# Status_Board.net
KiCad netlist of a schematic drawn in EAGLE
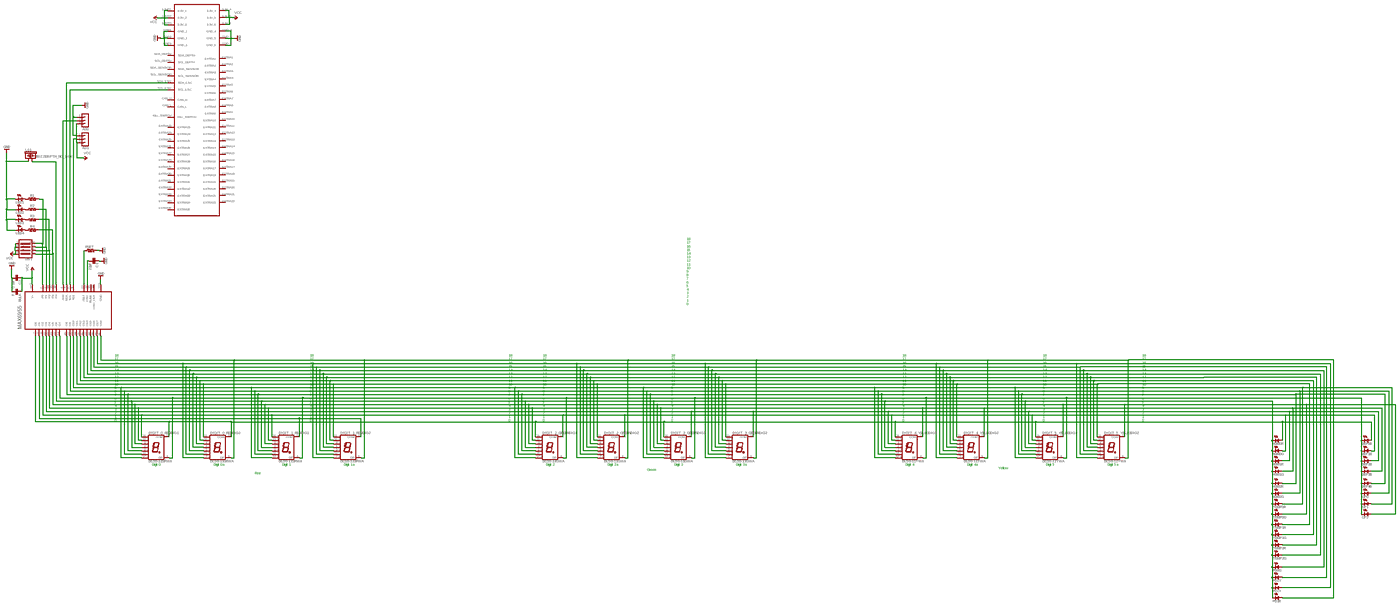
[diagram p0: schematic, sheet 1, overview]
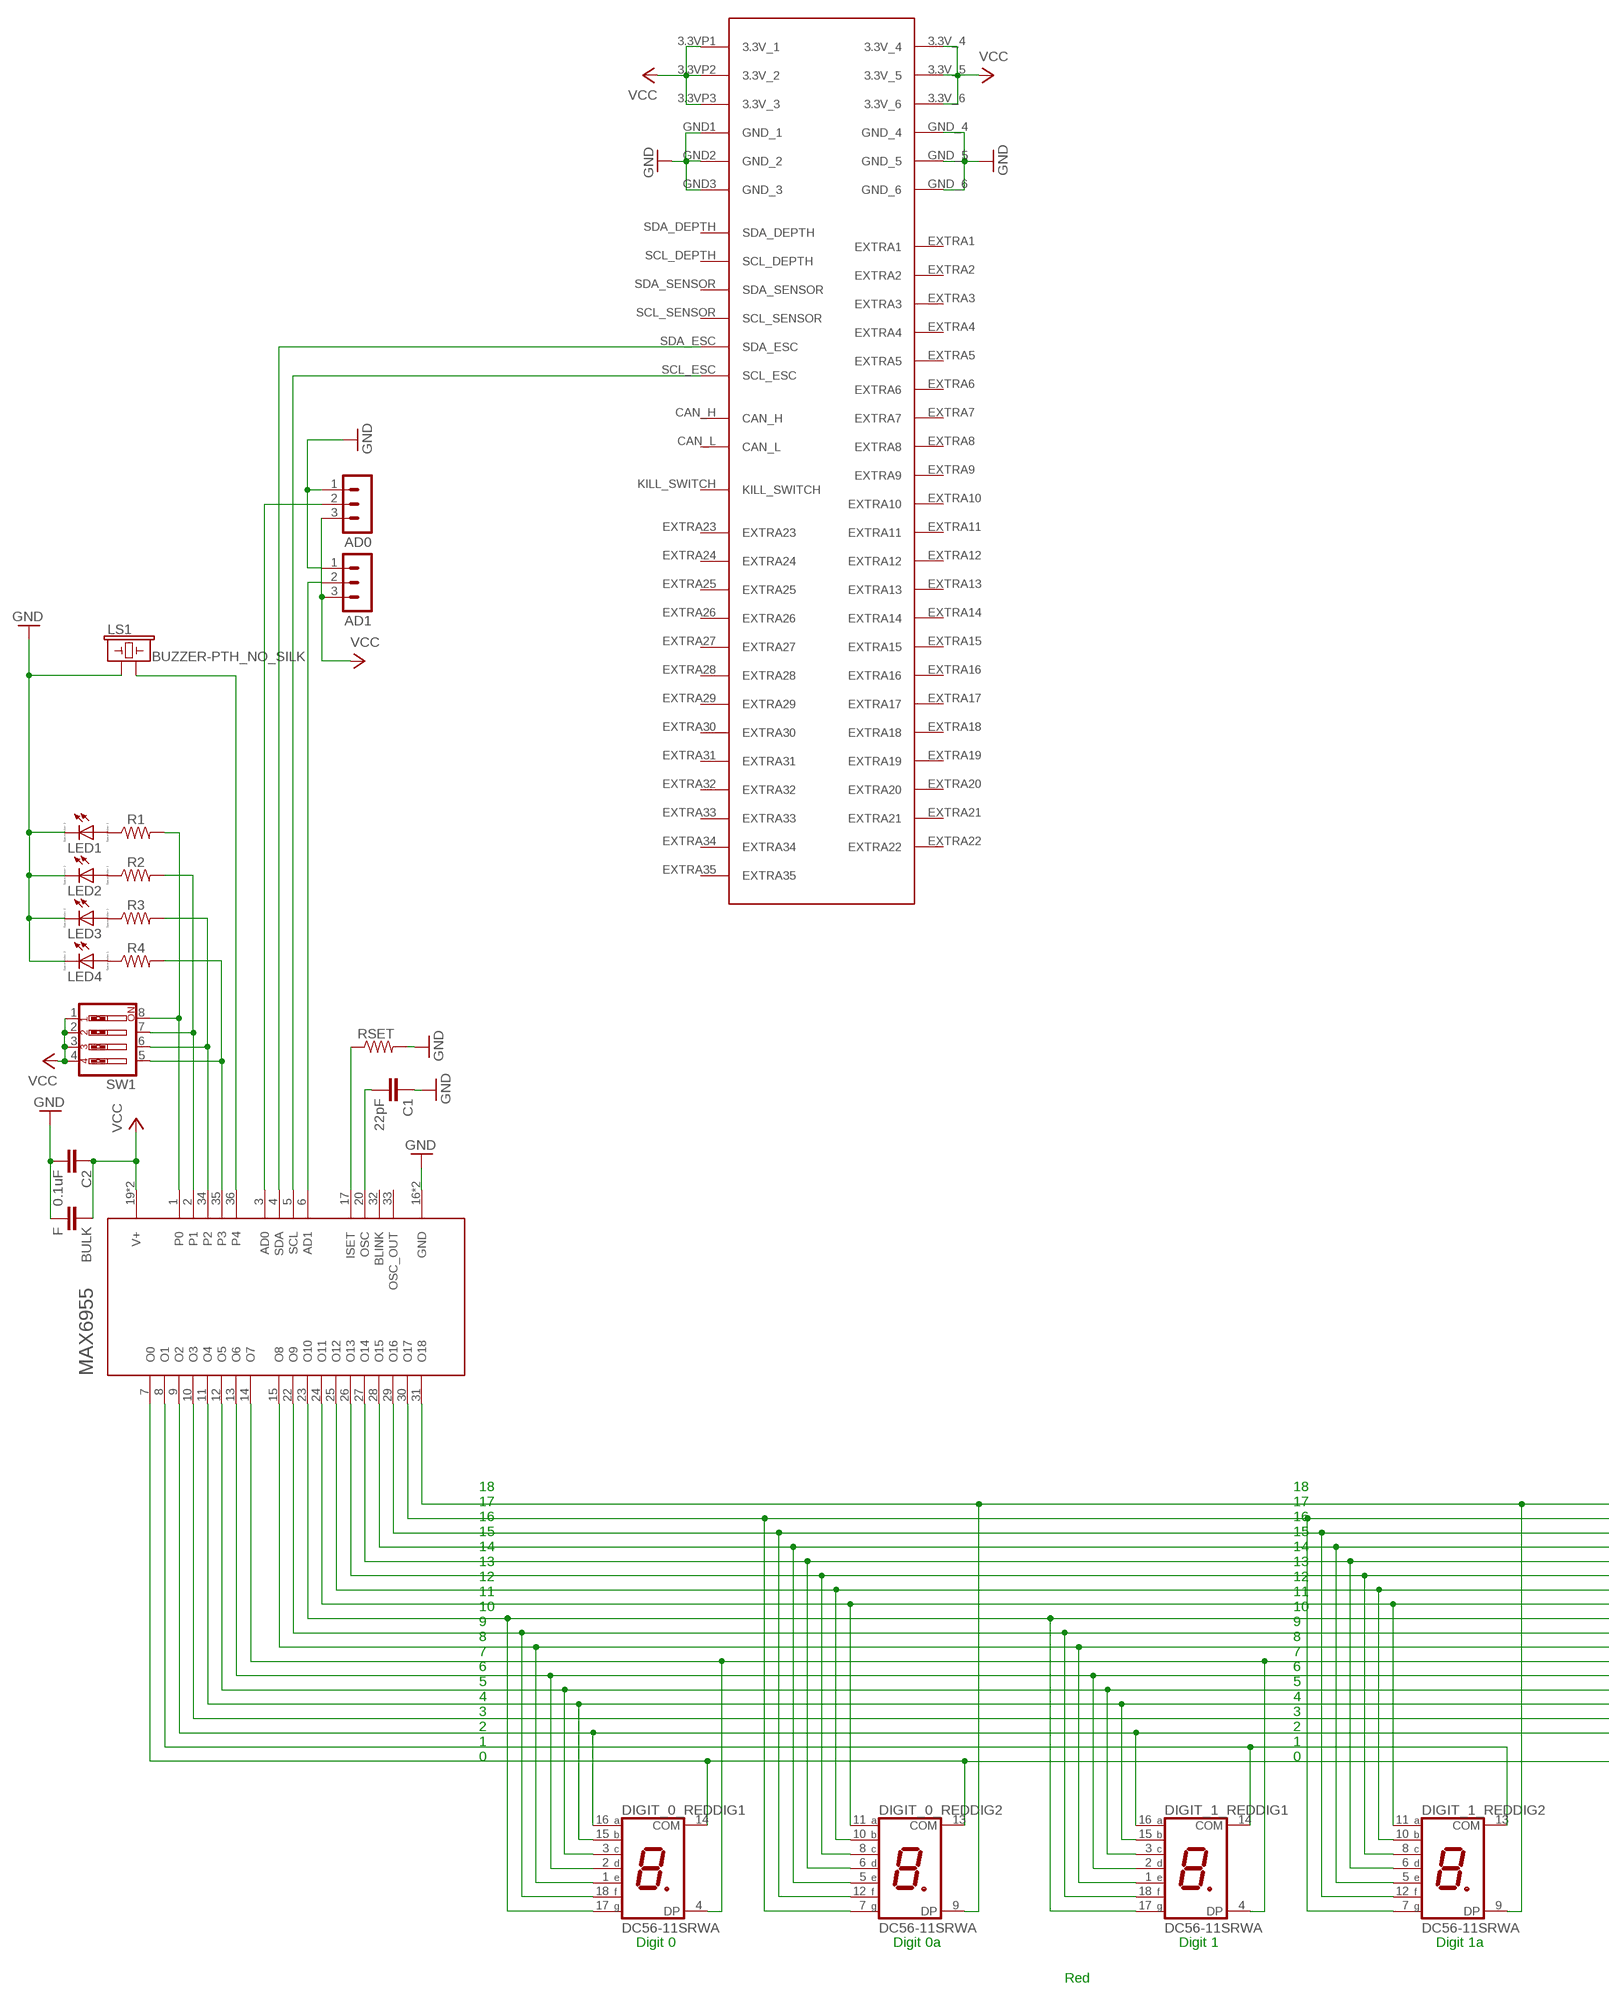
[diagram p1: schematic, sheet 1, part 1 of 4]
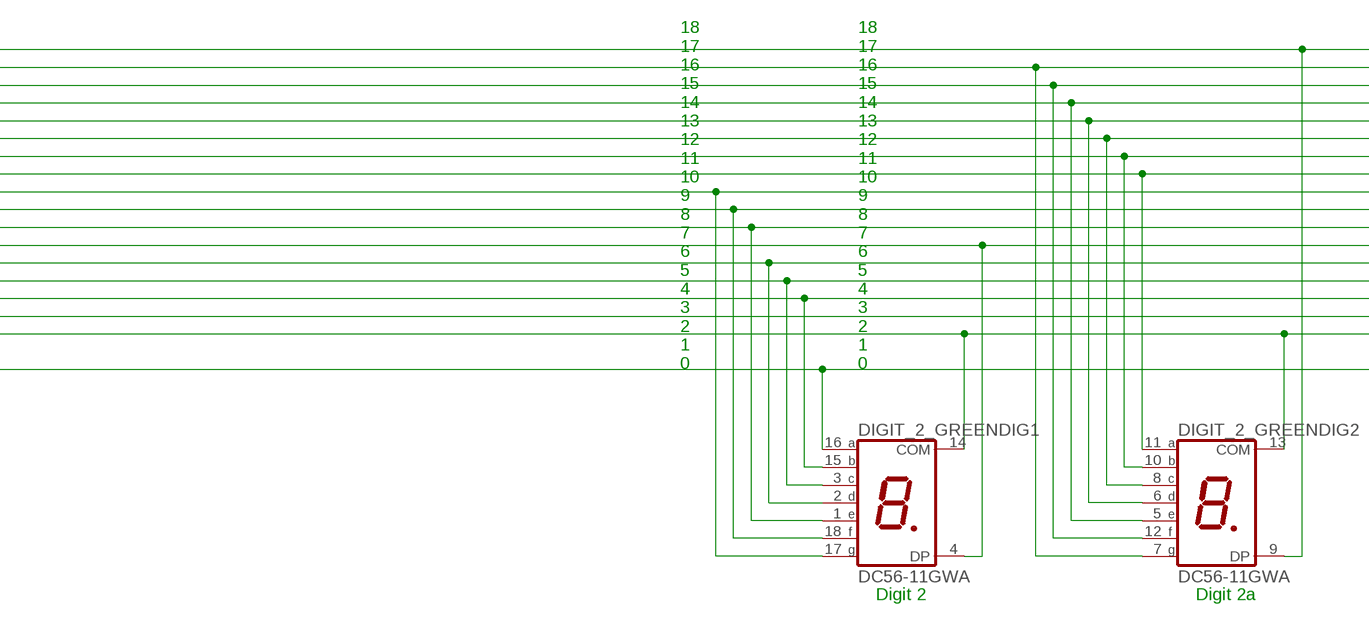
[diagram p2: schematic, sheet 1, part 2 of 4]
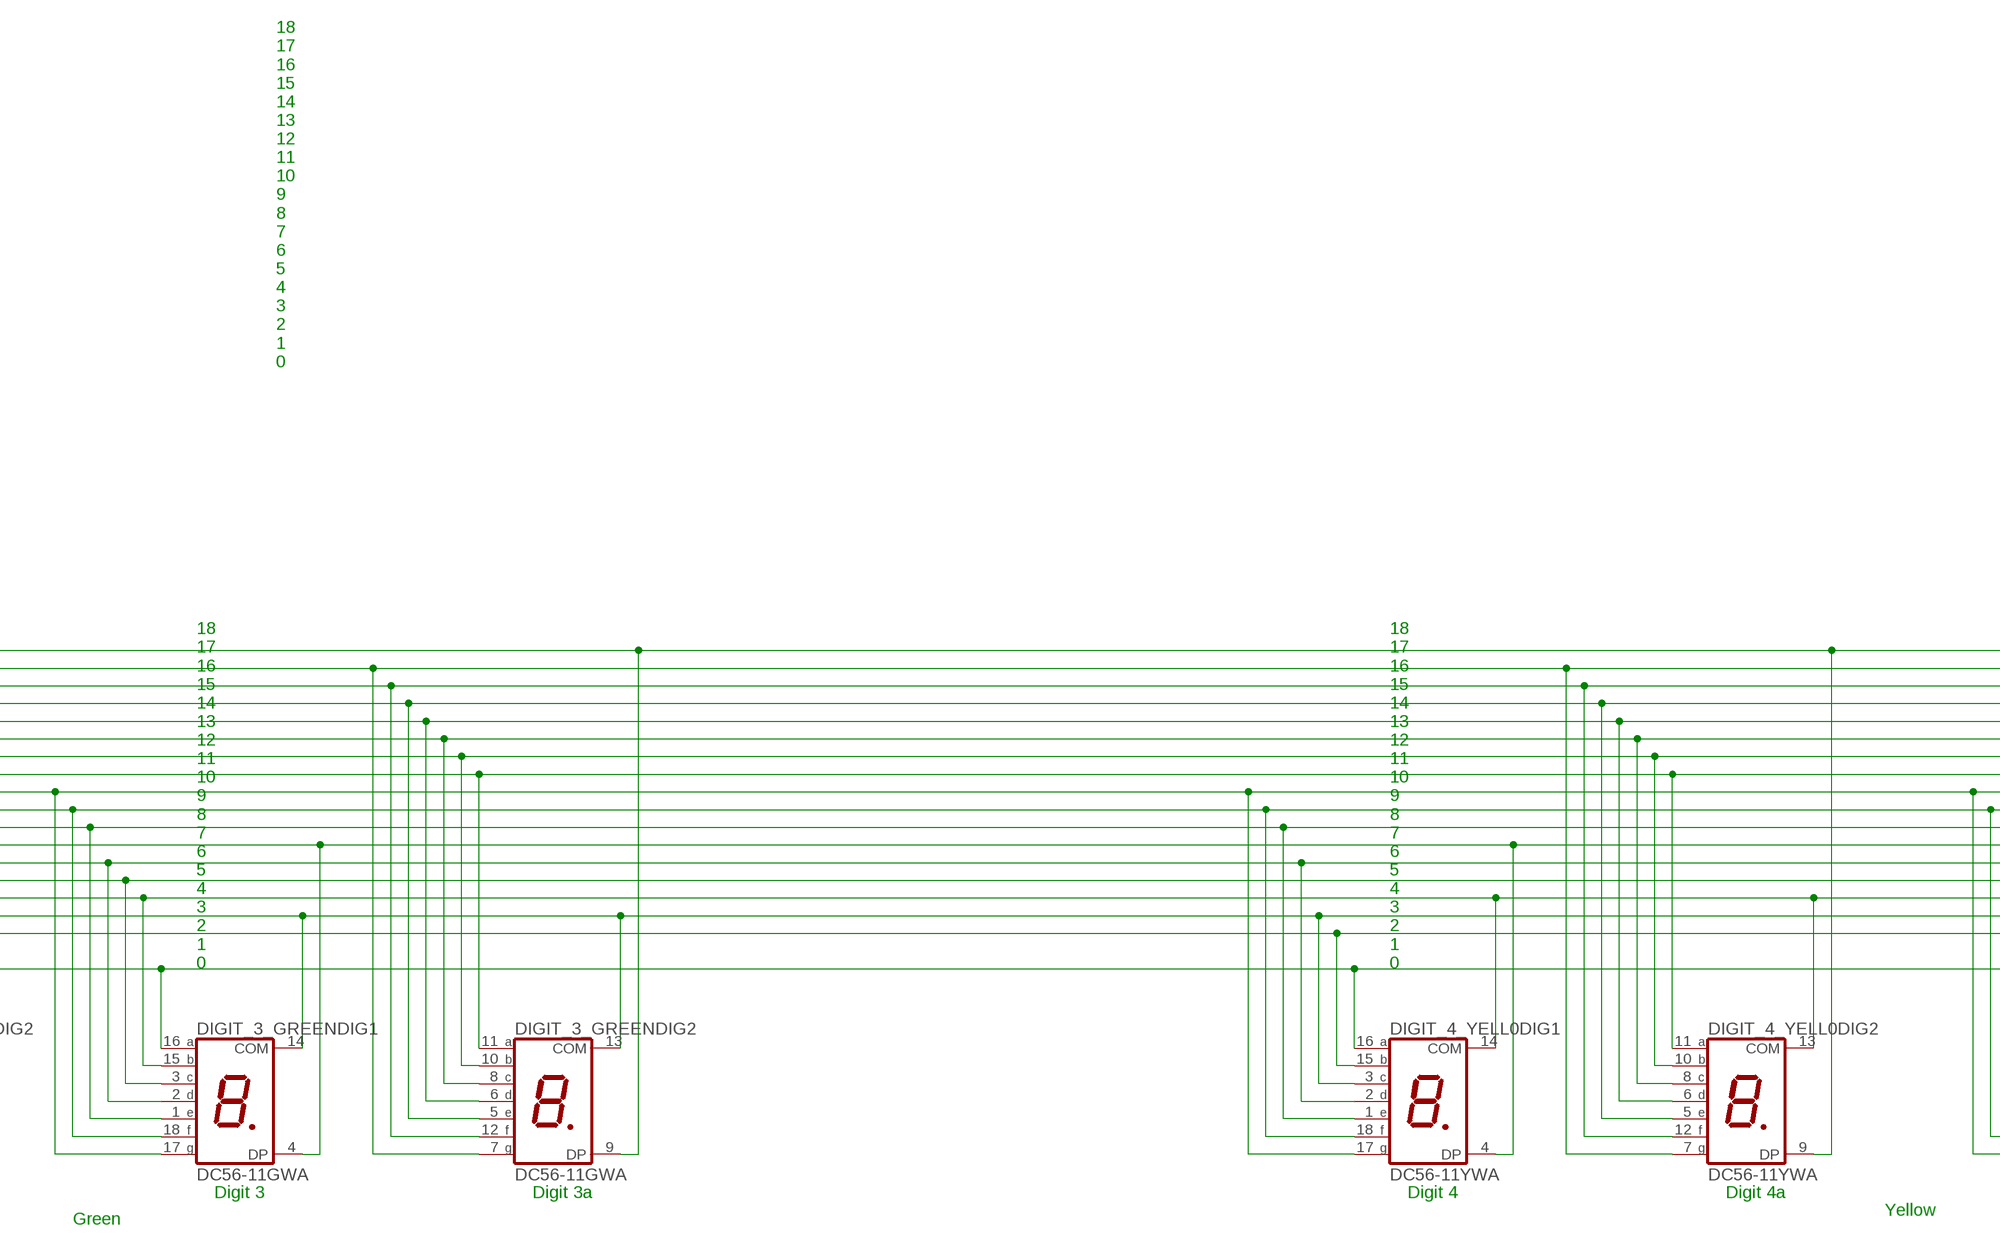
[diagram p3: schematic, sheet 1, part 3 of 4]
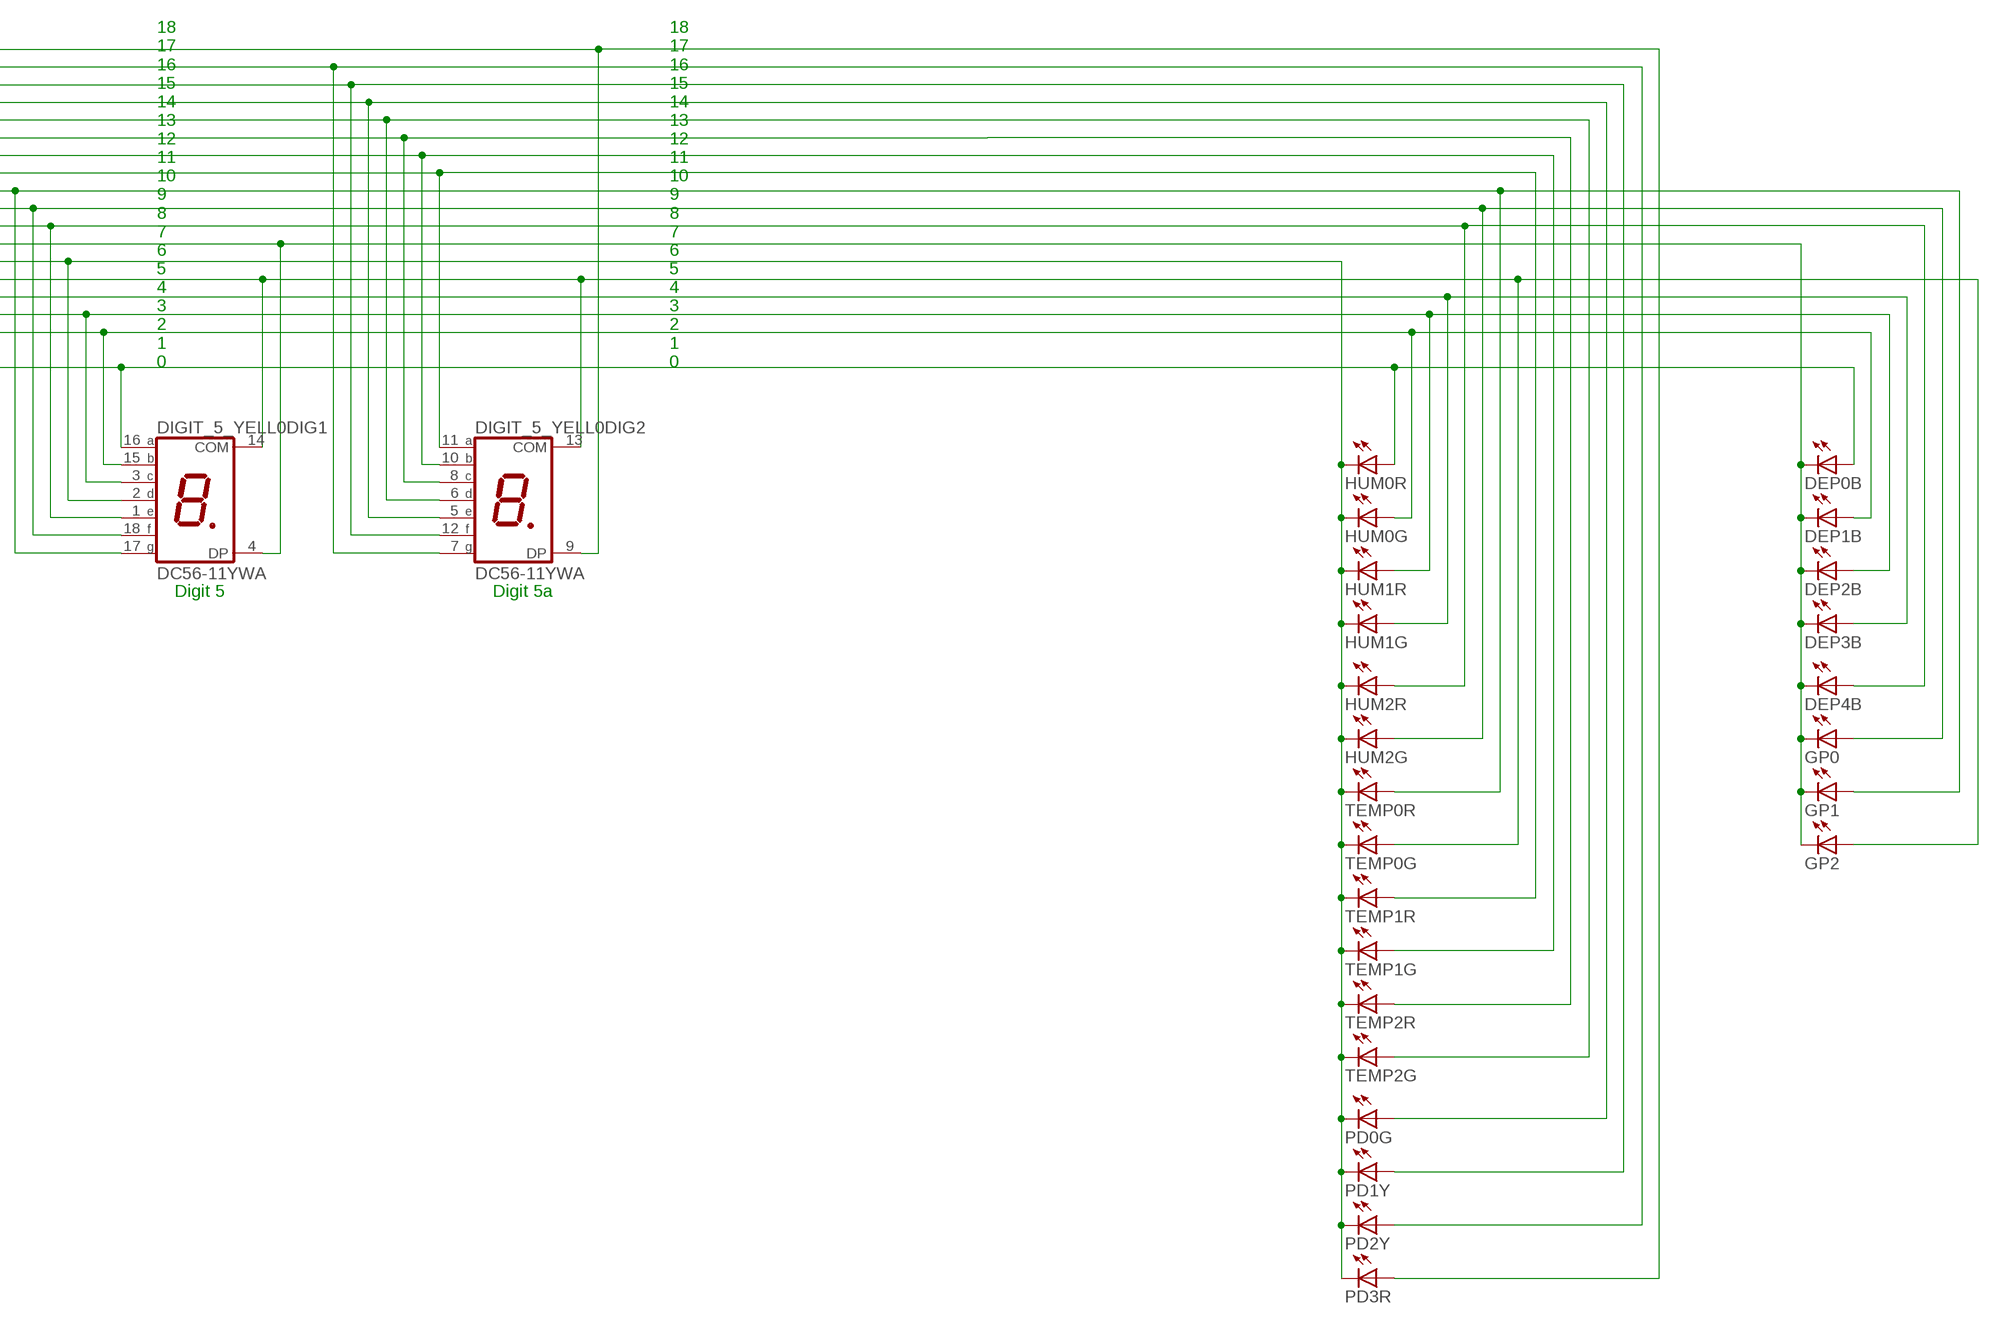
[diagram p4: schematic, sheet 1, part 4 of 4]

(export (version "E")
  (design (tool "Eeschema 10.0.6"))
  (components
    (comp (ref "AD0")
      (value "MA03-1")
      (footprint "eagle-import:MA03-1")
      (libsource (lib "eagle-import") (part "MA03-1"))
    )
    (comp (ref "AD1")
      (value "MA03-1")
      (footprint "eagle-import:MA03-1")
      (libsource (lib "eagle-import") (part "MA03-1"))
    )
    (comp (ref "BULK")
      (value "F")
      (footprint "eagle-import:CAP-PTH-SMALL-KIT")
      (libsource (lib "eagle-import") (part "0.1UF-KIT-EZ-50V-20%"))
    )
    (comp (ref "C1")
      (value "22pF")
      (footprint "eagle-import:CAP-PTH-2.54")
      (libsource (lib "eagle-import") (part "22PF-PTH-2.54MM-200V-5%"))
    )
    (comp (ref "C2")
      (value "0.1uF")
      (footprint "eagle-import:CAP-PTH-SMALL-KIT")
      (libsource (lib "eagle-import") (part "0.1UF-KIT-EZ-50V-20%"))
    )
    (comp (ref "DEP0B")
      (value "LED3MM")
      (footprint "eagle-import:LED3MM")
      (libsource (lib "eagle-import") (part "LED3MM"))
    )
    (comp (ref "DEP1B")
      (value "LED3MM")
      (footprint "eagle-import:LED3MM")
      (libsource (lib "eagle-import") (part "LED3MM"))
    )
    (comp (ref "DEP2B")
      (value "LED3MM")
      (footprint "eagle-import:LED3MM")
      (libsource (lib "eagle-import") (part "LED3MM"))
    )
    (comp (ref "DEP3B")
      (value "LED3MM")
      (footprint "eagle-import:LED3MM")
      (libsource (lib "eagle-import") (part "LED3MM"))
    )
    (comp (ref "DEP4B")
      (value "LED3MM")
      (footprint "eagle-import:LED3MM")
      (libsource (lib "eagle-import") (part "LED3MM"))
    )
    (comp (ref "DIGIT_0_RED")
      (value "DC56-11SRWA")
      (footprint "eagle-import:DA56")
      (libsource (lib "eagle-import") (part "DC56-11SRWA"))
    )
    (comp (ref "DIGIT_1_RED")
      (value "DC56-11SRWA")
      (footprint "eagle-import:DA56")
      (libsource (lib "eagle-import") (part "DC56-11SRWA"))
    )
    (comp (ref "DIGIT_2_GREEN")
      (value "DC56-11GWA")
      (footprint "eagle-import:DA56")
      (libsource (lib "eagle-import") (part "DC56-11GWA"))
    )
    (comp (ref "DIGIT_3_GREEN")
      (value "DC56-11GWA")
      (footprint "eagle-import:DA56")
      (libsource (lib "eagle-import") (part "DC56-11GWA"))
    )
    (comp (ref "DIGIT_4_YELL0")
      (value "DC56-11YWA")
      (footprint "eagle-import:DA56")
      (libsource (lib "eagle-import") (part "DC56-11YWA"))
    )
    (comp (ref "DIGIT_5_YELL0")
      (value "DC56-11YWA")
      (footprint "eagle-import:DA56")
      (libsource (lib "eagle-import") (part "DC56-11YWA"))
    )
    (comp (ref "GP0")
      (value "LED3MM")
      (footprint "eagle-import:LED3MM")
      (libsource (lib "eagle-import") (part "LED3MM"))
    )
    (comp (ref "GP1")
      (value "LED3MM")
      (footprint "eagle-import:LED3MM")
      (libsource (lib "eagle-import") (part "LED3MM"))
    )
    (comp (ref "GP2")
      (value "LED3MM")
      (footprint "eagle-import:LED3MM")
      (libsource (lib "eagle-import") (part "LED3MM"))
    )
    (comp (ref "HUM0G")
      (value "LED3MM")
      (footprint "eagle-import:LED3MM")
      (libsource (lib "eagle-import") (part "LED3MM"))
    )
    (comp (ref "HUM0R")
      (value "LED3MM")
      (footprint "eagle-import:LED3MM")
      (libsource (lib "eagle-import") (part "LED3MM"))
    )
    (comp (ref "HUM1G")
      (value "LED3MM")
      (footprint "eagle-import:LED3MM")
      (libsource (lib "eagle-import") (part "LED3MM"))
    )
    (comp (ref "HUM1R")
      (value "LED3MM")
      (footprint "eagle-import:LED3MM")
      (libsource (lib "eagle-import") (part "LED3MM"))
    )
    (comp (ref "HUM2G")
      (value "LED3MM")
      (footprint "eagle-import:LED3MM")
      (libsource (lib "eagle-import") (part "LED3MM"))
    )
    (comp (ref "HUM2R")
      (value "LED3MM")
      (footprint "eagle-import:LED3MM")
      (libsource (lib "eagle-import") (part "LED3MM"))
    )
    (comp (ref "LED1")
      (value "LED_ESML0603")
      (footprint "eagle-import:LED_SML0603")
      (libsource (lib "eagle-import") (part "LED_ESML0603"))
    )
    (comp (ref "LED2")
      (value "LED_ESML0603")
      (footprint "eagle-import:LED_SML0603")
      (libsource (lib "eagle-import") (part "LED_ESML0603"))
    )
    (comp (ref "LED3")
      (value "LED_ESML0603")
      (footprint "eagle-import:LED_SML0603")
      (libsource (lib "eagle-import") (part "LED_ESML0603"))
    )
    (comp (ref "LED4")
      (value "LED_ESML0603")
      (footprint "eagle-import:LED_SML0603")
      (libsource (lib "eagle-import") (part "LED_ESML0603"))
    )
    (comp (ref "LS1")
      (value "BUZZER-PTH_NO_SILK")
      (footprint "eagle-import:BUZZER-12MM-NS")
      (libsource (lib "eagle-import") (part "BUZZER-PTH_NO_SILK"))
    )
    (comp (ref "MAX6955")
      (value "MAX6955")
      (footprint "eagle-import:SSOP36")
      (libsource (lib "eagle-import") (part "MAX6955"))
    )
    (comp (ref "PD0G")
      (value "LED3MM")
      (footprint "eagle-import:LED3MM")
      (libsource (lib "eagle-import") (part "LED3MM"))
    )
    (comp (ref "PD1Y")
      (value "LED3MM")
      (footprint "eagle-import:LED3MM")
      (libsource (lib "eagle-import") (part "LED3MM"))
    )
    (comp (ref "PD2Y")
      (value "LED3MM")
      (footprint "eagle-import:LED3MM")
      (libsource (lib "eagle-import") (part "LED3MM"))
    )
    (comp (ref "PD3R")
      (value "LED3MM")
      (footprint "eagle-import:LED3MM")
      (libsource (lib "eagle-import") (part "LED3MM"))
    )
    (comp (ref "R1")
      (value "68OHM-0603-1/10W-1%")
      (footprint "eagle-import:0603")
      (libsource (lib "eagle-import") (part "68OHM-0603-1/10W-1%"))
    )
    (comp (ref "R2")
      (value "68OHM-0603-1/10W-1%")
      (footprint "eagle-import:0603")
      (libsource (lib "eagle-import") (part "68OHM-0603-1/10W-1%"))
    )
    (comp (ref "R3")
      (value "68OHM-0603-1/10W-1%")
      (footprint "eagle-import:0603")
      (libsource (lib "eagle-import") (part "68OHM-0603-1/10W-1%"))
    )
    (comp (ref "R4")
      (value "68OHM-0603-1/10W-1%")
      (footprint "eagle-import:0603")
      (libsource (lib "eagle-import") (part "68OHM-0603-1/10W-1%"))
    )
    (comp (ref "RSET")
      (value "R-US_0207/12")
      (footprint "eagle-import:0207_12")
      (libsource (lib "eagle-import") (part "R-US_0207/12"))
    )
    (comp (ref "SW1")
      (value "SW_DIP-4")
      (footprint "eagle-import:EDG-04")
      (libsource (lib "eagle-import") (part "SW_DIP-4"))
    )
    (comp (ref "TEMP0G")
      (value "LED3MM")
      (footprint "eagle-import:LED3MM")
      (libsource (lib "eagle-import") (part "LED3MM"))
    )
    (comp (ref "TEMP0R")
      (value "LED3MM")
      (footprint "eagle-import:LED3MM")
      (libsource (lib "eagle-import") (part "LED3MM"))
    )
    (comp (ref "TEMP1G")
      (value "LED3MM")
      (footprint "eagle-import:LED3MM")
      (libsource (lib "eagle-import") (part "LED3MM"))
    )
    (comp (ref "TEMP1R")
      (value "LED3MM")
      (footprint "eagle-import:LED3MM")
      (libsource (lib "eagle-import") (part "LED3MM"))
    )
    (comp (ref "TEMP2G")
      (value "LED3MM")
      (footprint "eagle-import:LED3MM")
      (libsource (lib "eagle-import") (part "LED3MM"))
    )
    (comp (ref "TEMP2R")
      (value "LED3MM")
      (footprint "eagle-import:LED3MM")
      (libsource (lib "eagle-import") (part "LED3MM"))
    )
    (comp (ref "U$2")
      (value "5530843")
      (footprint "eagle-import:5530843-6-BOARDFINGERS")
      (libsource (lib "eagle-import") (part "5530843"))
    )
  )
  (nets
    (net (code "1") (name "GND") (class "Default")
      (node (ref "AD0") (pin "1") (pinfunction "1_1") (pintype "passive"))
      (node (ref "AD1") (pin "1") (pinfunction "1_1") (pintype "passive"))
      (node (ref "BULK") (pin "2") (pinfunction "2_2") (pintype "passive"))
      (node (ref "C1") (pin "1") (pinfunction "1_1") (pintype "passive"))
      (node (ref "C2") (pin "2") (pinfunction "2_2") (pintype "passive"))
      (node (ref "LED1") (pin "C") (pinfunction "C_C") (pintype "passive"))
      (node (ref "LED2") (pin "C") (pinfunction "C_C") (pintype "passive"))
      (node (ref "LED3") (pin "C") (pinfunction "C_C") (pintype "passive"))
      (node (ref "LED4") (pin "C") (pinfunction "C_C") (pintype "passive"))
      (node (ref "LS1") (pin "+") (pinfunction "1_+") (pintype "passive"))
      (node (ref "MAX6955") (pin "16") (pinfunction "GND_16") (pintype "bidirectional"))
      (node (ref "MAX6955") (pin "18") (pinfunction "GND_18") (pintype "bidirectional"))
      (node (ref "RSET") (pin "2") (pinfunction "2_2") (pintype "passive"))
      (node (ref "U$2") (pin "GND1") (pinfunction "GND_1_GND1") (pintype "bidirectional"))
      (node (ref "U$2") (pin "GND2") (pinfunction "GND_2_GND2") (pintype "bidirectional"))
      (node (ref "U$2") (pin "GND3") (pinfunction "GND_3_GND3") (pintype "bidirectional"))
      (node (ref "U$2") (pin "GND_4") (pinfunction "GND_4_GND_4") (pintype "bidirectional"))
      (node (ref "U$2") (pin "GND_5") (pinfunction "GND_5_GND_5") (pintype "bidirectional"))
      (node (ref "U$2") (pin "GND_6") (pinfunction "GND_6_GND_6") (pintype "bidirectional"))
    )
    (net (code "2") (name "Net-(DEP0B-C)") (class "Default")
      (node (ref "DEP0B") (pin "K") (pinfunction "C_K") (pintype "passive"))
      (node (ref "DEP1B") (pin "K") (pinfunction "C_K") (pintype "passive"))
      (node (ref "DEP2B") (pin "K") (pinfunction "C_K") (pintype "passive"))
      (node (ref "DEP3B") (pin "K") (pinfunction "C_K") (pintype "passive"))
      (node (ref "DEP4B") (pin "K") (pinfunction "C_K") (pintype "passive"))
      (node (ref "DIGIT_0_RED") (pin "4") (pinfunction "DP_4") (pintype "passive"))
      (node (ref "DIGIT_1_RED") (pin "4") (pinfunction "DP_4") (pintype "passive"))
      (node (ref "DIGIT_2_GREEN") (pin "4") (pinfunction "DP_4") (pintype "passive"))
      (node (ref "DIGIT_3_GREEN") (pin "4") (pinfunction "DP_4") (pintype "passive"))
      (node (ref "DIGIT_4_YELL0") (pin "4") (pinfunction "DP_4") (pintype "passive"))
      (node (ref "DIGIT_5_YELL0") (pin "4") (pinfunction "DP_4") (pintype "passive"))
      (node (ref "GP0") (pin "K") (pinfunction "C_K") (pintype "passive"))
      (node (ref "GP1") (pin "K") (pinfunction "C_K") (pintype "passive"))
      (node (ref "GP2") (pin "K") (pinfunction "C_K") (pintype "passive"))
      (node (ref "MAX6955") (pin "14") (pinfunction "O7_14") (pintype "bidirectional"))
    )
    (net (code "3") (name "Net-(DIGIT_0_REDA-A)") (class "Default")
      (node (ref "DEP1B") (pin "A") (pinfunction "A_A") (pintype "passive"))
      (node (ref "DIGIT_0_RED") (pin "16") (pinfunction "A_16") (pintype "passive"))
      (node (ref "DIGIT_1_RED") (pin "16") (pinfunction "A_16") (pintype "passive"))
      (node (ref "DIGIT_2_GREEN") (pin "13") (pinfunction "COM_13") (pintype "passive"))
      (node (ref "DIGIT_2_GREEN") (pin "14") (pinfunction "COM_14") (pintype "passive"))
      (node (ref "DIGIT_4_YELL0") (pin "15") (pinfunction "B_15") (pintype "passive"))
      (node (ref "DIGIT_5_YELL0") (pin "15") (pinfunction "B_15") (pintype "passive"))
      (node (ref "HUM0G") (pin "A") (pinfunction "A_A") (pintype "passive"))
      (node (ref "MAX6955") (pin "9") (pinfunction "O2_9") (pintype "bidirectional"))
    )
    (net (code "4") (name "Net-(DIGIT_0_REDA-B)") (class "Default")
      (node (ref "DEP3B") (pin "A") (pinfunction "A_A") (pintype "passive"))
      (node (ref "DIGIT_0_RED") (pin "15") (pinfunction "B_15") (pintype "passive"))
      (node (ref "DIGIT_1_RED") (pin "15") (pinfunction "B_15") (pintype "passive"))
      (node (ref "DIGIT_2_GREEN") (pin "15") (pinfunction "B_15") (pintype "passive"))
      (node (ref "DIGIT_3_GREEN") (pin "15") (pinfunction "B_15") (pintype "passive"))
      (node (ref "DIGIT_4_YELL0") (pin "13") (pinfunction "COM_13") (pintype "passive"))
      (node (ref "DIGIT_4_YELL0") (pin "14") (pinfunction "COM_14") (pintype "passive"))
      (node (ref "HUM1G") (pin "A") (pinfunction "A_A") (pintype "passive"))
      (node (ref "MAX6955") (pin "11") (pinfunction "O4_11") (pintype "bidirectional"))
    )
    (net (code "5") (name "Net-(DIGIT_0_REDA-C)") (class "Default")
      (node (ref "DIGIT_0_RED") (pin "3") (pinfunction "C_3") (pintype "passive"))
      (node (ref "DIGIT_1_RED") (pin "3") (pinfunction "C_3") (pintype "passive"))
      (node (ref "DIGIT_2_GREEN") (pin "3") (pinfunction "C_3") (pintype "passive"))
      (node (ref "DIGIT_3_GREEN") (pin "3") (pinfunction "C_3") (pintype "passive"))
      (node (ref "DIGIT_5_YELL0") (pin "13") (pinfunction "COM_13") (pintype "passive"))
      (node (ref "DIGIT_5_YELL0") (pin "14") (pinfunction "COM_14") (pintype "passive"))
      (node (ref "GP2") (pin "A") (pinfunction "A_A") (pintype "passive"))
      (node (ref "MAX6955") (pin "12") (pinfunction "O5_12") (pintype "bidirectional"))
      (node (ref "TEMP0G") (pin "A") (pinfunction "A_A") (pintype "passive"))
    )
    (net (code "6") (name "Net-(DIGIT_0_REDA-COM)") (class "Default")
      (node (ref "DEP0B") (pin "A") (pinfunction "A_A") (pintype "passive"))
      (node (ref "DIGIT_0_RED") (pin "13") (pinfunction "COM_13") (pintype "passive"))
      (node (ref "DIGIT_0_RED") (pin "14") (pinfunction "COM_14") (pintype "passive"))
      (node (ref "DIGIT_2_GREEN") (pin "16") (pinfunction "A_16") (pintype "passive"))
      (node (ref "DIGIT_3_GREEN") (pin "16") (pinfunction "A_16") (pintype "passive"))
      (node (ref "DIGIT_4_YELL0") (pin "16") (pinfunction "A_16") (pintype "passive"))
      (node (ref "DIGIT_5_YELL0") (pin "16") (pinfunction "A_16") (pintype "passive"))
      (node (ref "HUM0R") (pin "A") (pinfunction "A_A") (pintype "passive"))
      (node (ref "MAX6955") (pin "7") (pinfunction "O0_7") (pintype "bidirectional"))
    )
    (net (code "7") (name "Net-(DIGIT_0_REDA-D)") (class "Default")
      (node (ref "DIGIT_0_RED") (pin "2") (pinfunction "D_2") (pintype "passive"))
      (node (ref "DIGIT_1_RED") (pin "2") (pinfunction "D_2") (pintype "passive"))
      (node (ref "DIGIT_2_GREEN") (pin "2") (pinfunction "D_2") (pintype "passive"))
      (node (ref "DIGIT_3_GREEN") (pin "2") (pinfunction "D_2") (pintype "passive"))
      (node (ref "DIGIT_4_YELL0") (pin "2") (pinfunction "D_2") (pintype "passive"))
      (node (ref "DIGIT_5_YELL0") (pin "2") (pinfunction "D_2") (pintype "passive"))
      (node (ref "HUM0G") (pin "K") (pinfunction "C_K") (pintype "passive"))
      (node (ref "HUM0R") (pin "K") (pinfunction "C_K") (pintype "passive"))
      (node (ref "HUM1G") (pin "K") (pinfunction "C_K") (pintype "passive"))
      (node (ref "HUM1R") (pin "K") (pinfunction "C_K") (pintype "passive"))
      (node (ref "HUM2G") (pin "K") (pinfunction "C_K") (pintype "passive"))
      (node (ref "HUM2R") (pin "K") (pinfunction "C_K") (pintype "passive"))
      (node (ref "MAX6955") (pin "13") (pinfunction "O6_13") (pintype "bidirectional"))
      (node (ref "PD0G") (pin "K") (pinfunction "C_K") (pintype "passive"))
      (node (ref "PD1Y") (pin "K") (pinfunction "C_K") (pintype "passive"))
      (node (ref "PD2Y") (pin "K") (pinfunction "C_K") (pintype "passive"))
      (node (ref "PD3R") (pin "K") (pinfunction "C_K") (pintype "passive"))
      (node (ref "TEMP0G") (pin "K") (pinfunction "C_K") (pintype "passive"))
      (node (ref "TEMP0R") (pin "K") (pinfunction "C_K") (pintype "passive"))
      (node (ref "TEMP1G") (pin "K") (pinfunction "C_K") (pintype "passive"))
      (node (ref "TEMP1R") (pin "K") (pinfunction "C_K") (pintype "passive"))
      (node (ref "TEMP2G") (pin "K") (pinfunction "C_K") (pintype "passive"))
      (node (ref "TEMP2R") (pin "K") (pinfunction "C_K") (pintype "passive"))
    )
    (net (code "8") (name "Net-(DIGIT_0_REDA-E)") (class "Default")
      (node (ref "DEP4B") (pin "A") (pinfunction "A_A") (pintype "passive"))
      (node (ref "DIGIT_0_RED") (pin "1") (pinfunction "E_1") (pintype "passive"))
      (node (ref "DIGIT_1_RED") (pin "1") (pinfunction "E_1") (pintype "passive"))
      (node (ref "DIGIT_2_GREEN") (pin "1") (pinfunction "E_1") (pintype "passive"))
      (node (ref "DIGIT_3_GREEN") (pin "1") (pinfunction "E_1") (pintype "passive"))
      (node (ref "DIGIT_4_YELL0") (pin "1") (pinfunction "E_1") (pintype "passive"))
      (node (ref "DIGIT_5_YELL0") (pin "1") (pinfunction "E_1") (pintype "passive"))
      (node (ref "HUM2R") (pin "A") (pinfunction "A_A") (pintype "passive"))
      (node (ref "MAX6955") (pin "15") (pinfunction "O8_15") (pintype "bidirectional"))
    )
    (net (code "9") (name "Net-(DIGIT_0_REDA-F)") (class "Default")
      (node (ref "DIGIT_0_RED") (pin "18") (pinfunction "F_18") (pintype "passive"))
      (node (ref "DIGIT_1_RED") (pin "18") (pinfunction "F_18") (pintype "passive"))
      (node (ref "DIGIT_2_GREEN") (pin "18") (pinfunction "F_18") (pintype "passive"))
      (node (ref "DIGIT_3_GREEN") (pin "18") (pinfunction "F_18") (pintype "passive"))
      (node (ref "DIGIT_4_YELL0") (pin "18") (pinfunction "F_18") (pintype "passive"))
      (node (ref "DIGIT_5_YELL0") (pin "18") (pinfunction "F_18") (pintype "passive"))
      (node (ref "GP0") (pin "A") (pinfunction "A_A") (pintype "passive"))
      (node (ref "HUM2G") (pin "A") (pinfunction "A_A") (pintype "passive"))
      (node (ref "MAX6955") (pin "22") (pinfunction "O9_22") (pintype "bidirectional"))
    )
    (net (code "10") (name "Net-(DIGIT_0_REDA-G)") (class "Default")
      (node (ref "DIGIT_0_RED") (pin "17") (pinfunction "G_17") (pintype "passive"))
      (node (ref "DIGIT_1_RED") (pin "17") (pinfunction "G_17") (pintype "passive"))
      (node (ref "DIGIT_2_GREEN") (pin "17") (pinfunction "G_17") (pintype "passive"))
      (node (ref "DIGIT_3_GREEN") (pin "17") (pinfunction "G_17") (pintype "passive"))
      (node (ref "DIGIT_4_YELL0") (pin "17") (pinfunction "G_17") (pintype "passive"))
      (node (ref "DIGIT_5_YELL0") (pin "17") (pinfunction "G_17") (pintype "passive"))
      (node (ref "GP1") (pin "A") (pinfunction "A_A") (pintype "passive"))
      (node (ref "MAX6955") (pin "23") (pinfunction "O10_23") (pintype "bidirectional"))
      (node (ref "TEMP0R") (pin "A") (pinfunction "A_A") (pintype "passive"))
    )
    (net (code "11") (name "Net-(DIGIT_0_REDB-A)") (class "Default")
      (node (ref "DIGIT_0_RED") (pin "11") (pinfunction "A_11") (pintype "passive"))
      (node (ref "DIGIT_1_RED") (pin "11") (pinfunction "A_11") (pintype "passive"))
      (node (ref "DIGIT_2_GREEN") (pin "11") (pinfunction "A_11") (pintype "passive"))
      (node (ref "DIGIT_3_GREEN") (pin "11") (pinfunction "A_11") (pintype "passive"))
      (node (ref "DIGIT_4_YELL0") (pin "11") (pinfunction "A_11") (pintype "passive"))
      (node (ref "DIGIT_5_YELL0") (pin "11") (pinfunction "A_11") (pintype "passive"))
      (node (ref "MAX6955") (pin "24") (pinfunction "O11_24") (pintype "bidirectional"))
      (node (ref "TEMP1R") (pin "A") (pinfunction "A_A") (pintype "passive"))
    )
    (net (code "12") (name "Net-(DIGIT_0_REDB-B)") (class "Default")
      (node (ref "DIGIT_0_RED") (pin "10") (pinfunction "B_10") (pintype "passive"))
      (node (ref "DIGIT_1_RED") (pin "10") (pinfunction "B_10") (pintype "passive"))
      (node (ref "DIGIT_2_GREEN") (pin "10") (pinfunction "B_10") (pintype "passive"))
      (node (ref "DIGIT_3_GREEN") (pin "10") (pinfunction "B_10") (pintype "passive"))
      (node (ref "DIGIT_4_YELL0") (pin "10") (pinfunction "B_10") (pintype "passive"))
      (node (ref "DIGIT_5_YELL0") (pin "10") (pinfunction "B_10") (pintype "passive"))
      (node (ref "MAX6955") (pin "25") (pinfunction "O12_25") (pintype "bidirectional"))
      (node (ref "TEMP1G") (pin "A") (pinfunction "A_A") (pintype "passive"))
    )
    (net (code "13") (name "Net-(DIGIT_0_REDB-C)") (class "Default")
      (node (ref "DIGIT_0_RED") (pin "8") (pinfunction "C_8") (pintype "passive"))
      (node (ref "DIGIT_1_RED") (pin "8") (pinfunction "C_8") (pintype "passive"))
      (node (ref "DIGIT_2_GREEN") (pin "8") (pinfunction "C_8") (pintype "passive"))
      (node (ref "DIGIT_3_GREEN") (pin "8") (pinfunction "C_8") (pintype "passive"))
      (node (ref "DIGIT_4_YELL0") (pin "8") (pinfunction "C_8") (pintype "passive"))
      (node (ref "DIGIT_5_YELL0") (pin "8") (pinfunction "C_8") (pintype "passive"))
      (node (ref "MAX6955") (pin "26") (pinfunction "O13_26") (pintype "bidirectional"))
      (node (ref "TEMP2R") (pin "A") (pinfunction "A_A") (pintype "passive"))
    )
    (net (code "14") (name "Net-(DIGIT_0_REDB-D)") (class "Default")
      (node (ref "DIGIT_0_RED") (pin "6") (pinfunction "D_6") (pintype "passive"))
      (node (ref "DIGIT_1_RED") (pin "6") (pinfunction "D_6") (pintype "passive"))
      (node (ref "DIGIT_2_GREEN") (pin "6") (pinfunction "D_6") (pintype "passive"))
      (node (ref "DIGIT_3_GREEN") (pin "6") (pinfunction "D_6") (pintype "passive"))
      (node (ref "DIGIT_4_YELL0") (pin "6") (pinfunction "D_6") (pintype "passive"))
      (node (ref "DIGIT_5_YELL0") (pin "6") (pinfunction "D_6") (pintype "passive"))
      (node (ref "MAX6955") (pin "27") (pinfunction "O14_27") (pintype "bidirectional"))
      (node (ref "TEMP2G") (pin "A") (pinfunction "A_A") (pintype "passive"))
    )
    (net (code "15") (name "Net-(DIGIT_0_REDB-DP)") (class "Default")
      (node (ref "DIGIT_0_RED") (pin "9") (pinfunction "DP_9") (pintype "passive"))
      (node (ref "DIGIT_1_RED") (pin "9") (pinfunction "DP_9") (pintype "passive"))
      (node (ref "DIGIT_2_GREEN") (pin "9") (pinfunction "DP_9") (pintype "passive"))
      (node (ref "DIGIT_3_GREEN") (pin "9") (pinfunction "DP_9") (pintype "passive"))
      (node (ref "DIGIT_4_YELL0") (pin "9") (pinfunction "DP_9") (pintype "passive"))
      (node (ref "DIGIT_5_YELL0") (pin "9") (pinfunction "DP_9") (pintype "passive"))
      (node (ref "MAX6955") (pin "31") (pinfunction "O18_31") (pintype "bidirectional"))
      (node (ref "PD3R") (pin "A") (pinfunction "A_A") (pintype "passive"))
    )
    (net (code "16") (name "Net-(DIGIT_0_REDB-E)") (class "Default")
      (node (ref "DIGIT_0_RED") (pin "5") (pinfunction "E_5") (pintype "passive"))
      (node (ref "DIGIT_1_RED") (pin "5") (pinfunction "E_5") (pintype "passive"))
      (node (ref "DIGIT_2_GREEN") (pin "5") (pinfunction "E_5") (pintype "passive"))
      (node (ref "DIGIT_3_GREEN") (pin "5") (pinfunction "E_5") (pintype "passive"))
      (node (ref "DIGIT_4_YELL0") (pin "5") (pinfunction "E_5") (pintype "passive"))
      (node (ref "DIGIT_5_YELL0") (pin "5") (pinfunction "E_5") (pintype "passive"))
      (node (ref "MAX6955") (pin "28") (pinfunction "O15_28") (pintype "bidirectional"))
      (node (ref "PD0G") (pin "A") (pinfunction "A_A") (pintype "passive"))
    )
    (net (code "17") (name "Net-(DIGIT_0_REDB-F)") (class "Default")
      (node (ref "DIGIT_0_RED") (pin "12") (pinfunction "F_12") (pintype "passive"))
      (node (ref "DIGIT_1_RED") (pin "12") (pinfunction "F_12") (pintype "passive"))
      (node (ref "DIGIT_2_GREEN") (pin "12") (pinfunction "F_12") (pintype "passive"))
      (node (ref "DIGIT_3_GREEN") (pin "12") (pinfunction "F_12") (pintype "passive"))
      (node (ref "DIGIT_4_YELL0") (pin "12") (pinfunction "F_12") (pintype "passive"))
      (node (ref "DIGIT_5_YELL0") (pin "12") (pinfunction "F_12") (pintype "passive"))
      (node (ref "MAX6955") (pin "29") (pinfunction "O16_29") (pintype "bidirectional"))
      (node (ref "PD1Y") (pin "A") (pinfunction "A_A") (pintype "passive"))
    )
    (net (code "18") (name "Net-(DIGIT_0_REDB-G)") (class "Default")
      (node (ref "DIGIT_0_RED") (pin "7") (pinfunction "G_7") (pintype "passive"))
      (node (ref "DIGIT_1_RED") (pin "7") (pinfunction "G_7") (pintype "passive"))
      (node (ref "DIGIT_2_GREEN") (pin "7") (pinfunction "G_7") (pintype "passive"))
      (node (ref "DIGIT_3_GREEN") (pin "7") (pinfunction "G_7") (pintype "passive"))
      (node (ref "DIGIT_4_YELL0") (pin "7") (pinfunction "G_7") (pintype "passive"))
      (node (ref "DIGIT_5_YELL0") (pin "7") (pinfunction "G_7") (pintype "passive"))
      (node (ref "MAX6955") (pin "30") (pinfunction "O17_30") (pintype "bidirectional"))
      (node (ref "PD2Y") (pin "A") (pinfunction "A_A") (pintype "passive"))
    )
    (net (code "19") (name "Net-(DIGIT_1_REDA-COM)") (class "Default")
      (node (ref "DIGIT_1_RED") (pin "13") (pinfunction "COM_13") (pintype "passive"))
      (node (ref "DIGIT_1_RED") (pin "14") (pinfunction "COM_14") (pintype "passive"))
      (node (ref "MAX6955") (pin "8") (pinfunction "O1_8") (pintype "bidirectional"))
    )
    (net (code "20") (name "Net-(DIGIT_3_GREENA-COM)") (class "Default")
      (node (ref "DEP2B") (pin "A") (pinfunction "A_A") (pintype "passive"))
      (node (ref "DIGIT_3_GREEN") (pin "13") (pinfunction "COM_13") (pintype "passive"))
      (node (ref "DIGIT_3_GREEN") (pin "14") (pinfunction "COM_14") (pintype "passive"))
      (node (ref "DIGIT_4_YELL0") (pin "3") (pinfunction "C_3") (pintype "passive"))
      (node (ref "DIGIT_5_YELL0") (pin "3") (pinfunction "C_3") (pintype "passive"))
      (node (ref "HUM1R") (pin "A") (pinfunction "A_A") (pintype "passive"))
      (node (ref "MAX6955") (pin "10") (pinfunction "O3_10") (pintype "bidirectional"))
    )
    (net (code "21") (name "Net-(LED1-PadA)") (class "Default")
      (node (ref "LED1") (pin "A") (pinfunction "A_A") (pintype "passive"))
      (node (ref "R1") (pin "1") (pinfunction "1_1") (pintype "passive"))
    )
    (net (code "22") (name "Net-(LED2-PadA)") (class "Default")
      (node (ref "LED2") (pin "A") (pinfunction "A_A") (pintype "passive"))
      (node (ref "R2") (pin "1") (pinfunction "1_1") (pintype "passive"))
    )
    (net (code "23") (name "Net-(LED3-PadA)") (class "Default")
      (node (ref "LED3") (pin "A") (pinfunction "A_A") (pintype "passive"))
      (node (ref "R3") (pin "1") (pinfunction "1_1") (pintype "passive"))
    )
    (net (code "24") (name "Net-(LED4-PadA)") (class "Default")
      (node (ref "LED4") (pin "A") (pinfunction "A_A") (pintype "passive"))
      (node (ref "R4") (pin "1") (pinfunction "1_1") (pintype "passive"))
    )
    (net (code "25") (name "Net-(LS1-2)") (class "Default")
      (node (ref "LS1") (pin "-") (pinfunction "2_-") (pintype "passive"))
      (node (ref "MAX6955") (pin "36") (pinfunction "P4_36") (pintype "bidirectional"))
    )
    (net (code "26") (name "Net-(MAX6955-AD0)") (class "Default")
      (node (ref "AD0") (pin "2") (pinfunction "2_2") (pintype "passive"))
      (node (ref "MAX6955") (pin "3") (pinfunction "AD0_3") (pintype "bidirectional"))
    )
    (net (code "27") (name "Net-(MAX6955-AD1)") (class "Default")
      (node (ref "AD1") (pin "2") (pinfunction "2_2") (pintype "passive"))
      (node (ref "MAX6955") (pin "6") (pinfunction "AD1_6") (pintype "bidirectional"))
    )
    (net (code "28") (name "Net-(MAX6955-ISET)") (class "Default")
      (node (ref "MAX6955") (pin "17") (pinfunction "ISET_17") (pintype "bidirectional"))
      (node (ref "RSET") (pin "1") (pinfunction "1_1") (pintype "passive"))
    )
    (net (code "29") (name "Net-(MAX6955-OSC)") (class "Default")
      (node (ref "C1") (pin "2") (pinfunction "2_2") (pintype "passive"))
      (node (ref "MAX6955") (pin "20") (pinfunction "OSC_20") (pintype "bidirectional"))
    )
    (net (code "30") (name "Net-(MAX6955-P0)") (class "Default")
      (node (ref "MAX6955") (pin "1") (pinfunction "P0_1") (pintype "bidirectional"))
      (node (ref "R1") (pin "2") (pinfunction "2_2") (pintype "passive"))
      (node (ref "SW1") (pin "8") (pinfunction "8_8") (pintype "passive"))
    )
    (net (code "31") (name "Net-(MAX6955-P1)") (class "Default")
      (node (ref "MAX6955") (pin "2") (pinfunction "P1_2") (pintype "bidirectional"))
      (node (ref "R2") (pin "2") (pinfunction "2_2") (pintype "passive"))
      (node (ref "SW1") (pin "7") (pinfunction "7_7") (pintype "passive"))
    )
    (net (code "32") (name "Net-(MAX6955-P2)") (class "Default")
      (node (ref "MAX6955") (pin "34") (pinfunction "P2_34") (pintype "bidirectional"))
      (node (ref "R3") (pin "2") (pinfunction "2_2") (pintype "passive"))
      (node (ref "SW1") (pin "6") (pinfunction "6_6") (pintype "passive"))
    )
    (net (code "33") (name "Net-(MAX6955-P3)") (class "Default")
      (node (ref "MAX6955") (pin "35") (pinfunction "P3_35") (pintype "bidirectional"))
      (node (ref "R4") (pin "2") (pinfunction "2_2") (pintype "passive"))
      (node (ref "SW1") (pin "5") (pinfunction "5_5") (pintype "passive"))
    )
    (net (code "34") (name "Net-(MAX6955-SCL)") (class "Default")
      (node (ref "MAX6955") (pin "5") (pinfunction "SCL_5") (pintype "bidirectional"))
      (node (ref "U$2") (pin "SCL_ESC") (pinfunction "SCL_ESC_SCL_ESC") (pintype "bidirectional"))
    )
    (net (code "35") (name "Net-(MAX6955-SDA)") (class "Default")
      (node (ref "MAX6955") (pin "4") (pinfunction "SDA_4") (pintype "bidirectional"))
      (node (ref "U$2") (pin "SDA_ESC") (pinfunction "SDA_ESC_SDA_ESC") (pintype "bidirectional"))
    )
    (net (code "36") (name "VCC") (class "Default")
      (node (ref "AD0") (pin "3") (pinfunction "3_3") (pintype "passive"))
      (node (ref "AD1") (pin "3") (pinfunction "3_3") (pintype "passive"))
      (node (ref "BULK") (pin "1") (pinfunction "1_1") (pintype "passive"))
      (node (ref "C2") (pin "1") (pinfunction "1_1") (pintype "passive"))
      (node (ref "MAX6955") (pin "19") (pinfunction "V+_19") (pintype "bidirectional"))
      (node (ref "MAX6955") (pin "21") (pinfunction "V+_21") (pintype "bidirectional"))
      (node (ref "SW1") (pin "1") (pinfunction "1_1") (pintype "passive"))
      (node (ref "SW1") (pin "2") (pinfunction "2_2") (pintype "passive"))
      (node (ref "SW1") (pin "3") (pinfunction "3_3") (pintype "passive"))
      (node (ref "SW1") (pin "4") (pinfunction "4_4") (pintype "passive"))
      (node (ref "U$2") (pin "3.3VP1") (pinfunction "3.3V_1_3.3VP1") (pintype "bidirectional"))
      (node (ref "U$2") (pin "3.3VP2") (pinfunction "3.3V_2_3.3VP2") (pintype "bidirectional"))
      (node (ref "U$2") (pin "3.3VP3") (pinfunction "3.3V_3_3.3VP3") (pintype "bidirectional"))
      (node (ref "U$2") (pin "3.3V_4") (pinfunction "3.3V_4_3.3V_4") (pintype "bidirectional"))
      (node (ref "U$2") (pin "3.3V_5") (pinfunction "3.3V_5_3.3V_5") (pintype "bidirectional"))
      (node (ref "U$2") (pin "3.3V_6") (pinfunction "3.3V_6_3.3V_6") (pintype "bidirectional"))
    )
    (net (code "37") (name "unconnected-(MAX6955-BLINK-Pad32)") (class "Default")
      (node (ref "MAX6955") (pin "32") (pinfunction "BLINK_32") (pintype "bidirectional"))
    )
    (net (code "38") (name "unconnected-(MAX6955-OSC_OUT-Pad33)") (class "Default")
      (node (ref "MAX6955") (pin "33") (pinfunction "OSC_OUT_33") (pintype "bidirectional"))
    )
    (net (code "39") (name "unconnected-(U$2-PadCAN_H)") (class "Default")
      (node (ref "U$2") (pin "CAN_H") (pinfunction "CAN_H_CAN_H") (pintype "bidirectional"))
    )
    (net (code "40") (name "unconnected-(U$2-PadCAN_L)") (class "Default")
      (node (ref "U$2") (pin "CAN_L") (pinfunction "CAN_L_CAN_L") (pintype "bidirectional"))
    )
    (net (code "41") (name "unconnected-(U$2-PadEXTRA1)") (class "Default")
      (node (ref "U$2") (pin "EXTRA1") (pinfunction "EXTRA1_EXTRA1") (pintype "bidirectional"))
    )
    (net (code "42") (name "unconnected-(U$2-PadEXTRA2)") (class "Default")
      (node (ref "U$2") (pin "EXTRA2") (pinfunction "EXTRA2_EXTRA2") (pintype "bidirectional"))
    )
    (net (code "43") (name "unconnected-(U$2-PadEXTRA3)") (class "Default")
      (node (ref "U$2") (pin "EXTRA3") (pinfunction "EXTRA3_EXTRA3") (pintype "bidirectional"))
    )
    (net (code "44") (name "unconnected-(U$2-PadEXTRA4)") (class "Default")
      (node (ref "U$2") (pin "EXTRA4") (pinfunction "EXTRA4_EXTRA4") (pintype "bidirectional"))
    )
    (net (code "45") (name "unconnected-(U$2-PadEXTRA5)") (class "Default")
      (node (ref "U$2") (pin "EXTRA5") (pinfunction "EXTRA5_EXTRA5") (pintype "bidirectional"))
    )
    (net (code "46") (name "unconnected-(U$2-PadEXTRA6)") (class "Default")
      (node (ref "U$2") (pin "EXTRA6") (pinfunction "EXTRA6_EXTRA6") (pintype "bidirectional"))
    )
    (net (code "47") (name "unconnected-(U$2-PadEXTRA7)") (class "Default")
      (node (ref "U$2") (pin "EXTRA7") (pinfunction "EXTRA7_EXTRA7") (pintype "bidirectional"))
    )
    (net (code "48") (name "unconnected-(U$2-PadEXTRA8)") (class "Default")
      (node (ref "U$2") (pin "EXTRA8") (pinfunction "EXTRA8_EXTRA8") (pintype "bidirectional"))
    )
    (net (code "49") (name "unconnected-(U$2-PadEXTRA9)") (class "Default")
      (node (ref "U$2") (pin "EXTRA9") (pinfunction "EXTRA9_EXTRA9") (pintype "bidirectional"))
    )
    (net (code "50") (name "unconnected-(U$2-PadEXTRA10)") (class "Default")
      (node (ref "U$2") (pin "EXTRA10") (pinfunction "EXTRA10_EXTRA10") (pintype "bidirectional"))
    )
    (net (code "51") (name "unconnected-(U$2-PadEXTRA11)") (class "Default")
      (node (ref "U$2") (pin "EXTRA11") (pinfunction "EXTRA11_EXTRA11") (pintype "bidirectional"))
    )
    (net (code "52") (name "unconnected-(U$2-PadEXTRA12)") (class "Default")
      (node (ref "U$2") (pin "EXTRA12") (pinfunction "EXTRA12_EXTRA12") (pintype "bidirectional"))
    )
    (net (code "53") (name "unconnected-(U$2-PadEXTRA13)") (class "Default")
      (node (ref "U$2") (pin "EXTRA13") (pinfunction "EXTRA13_EXTRA13") (pintype "bidirectional"))
    )
    (net (code "54") (name "unconnected-(U$2-PadEXTRA14)") (class "Default")
      (node (ref "U$2") (pin "EXTRA14") (pinfunction "EXTRA14_EXTRA14") (pintype "bidirectional"))
    )
    (net (code "55") (name "unconnected-(U$2-PadEXTRA15)") (class "Default")
      (node (ref "U$2") (pin "EXTRA15") (pinfunction "EXTRA15_EXTRA15") (pintype "bidirectional"))
    )
    (net (code "56") (name "unconnected-(U$2-PadEXTRA16)") (class "Default")
      (node (ref "U$2") (pin "EXTRA16") (pinfunction "EXTRA16_EXTRA16") (pintype "bidirectional"))
    )
    (net (code "57") (name "unconnected-(U$2-PadEXTRA17)") (class "Default")
      (node (ref "U$2") (pin "EXTRA17") (pinfunction "EXTRA17_EXTRA17") (pintype "bidirectional"))
    )
    (net (code "58") (name "unconnected-(U$2-PadEXTRA18)") (class "Default")
      (node (ref "U$2") (pin "EXTRA18") (pinfunction "EXTRA18_EXTRA18") (pintype "bidirectional"))
    )
    (net (code "59") (name "unconnected-(U$2-PadEXTRA19)") (class "Default")
      (node (ref "U$2") (pin "EXTRA19") (pinfunction "EXTRA19_EXTRA19") (pintype "bidirectional"))
    )
    (net (code "60") (name "unconnected-(U$2-PadEXTRA20)") (class "Default")
      (node (ref "U$2") (pin "EXTRA20") (pinfunction "EXTRA20_EXTRA20") (pintype "bidirectional"))
    )
    (net (code "61") (name "unconnected-(U$2-PadEXTRA21)") (class "Default")
      (node (ref "U$2") (pin "EXTRA21") (pinfunction "EXTRA21_EXTRA21") (pintype "bidirectional"))
    )
    (net (code "62") (name "unconnected-(U$2-PadEXTRA22)") (class "Default")
      (node (ref "U$2") (pin "EXTRA22") (pinfunction "EXTRA22_EXTRA22") (pintype "bidirectional"))
    )
    (net (code "63") (name "unconnected-(U$2-PadEXTRA23)") (class "Default")
      (node (ref "U$2") (pin "EXTRA23") (pinfunction "EXTRA23_EXTRA23") (pintype "bidirectional"))
    )
    (net (code "64") (name "unconnected-(U$2-PadEXTRA24)") (class "Default")
      (node (ref "U$2") (pin "EXTRA24") (pinfunction "EXTRA24_EXTRA24") (pintype "bidirectional"))
    )
    (net (code "65") (name "unconnected-(U$2-PadEXTRA25)") (class "Default")
      (node (ref "U$2") (pin "EXTRA25") (pinfunction "EXTRA25_EXTRA25") (pintype "bidirectional"))
    )
    (net (code "66") (name "unconnected-(U$2-PadEXTRA26)") (class "Default")
      (node (ref "U$2") (pin "EXTRA26") (pinfunction "EXTRA26_EXTRA26") (pintype "bidirectional"))
    )
    (net (code "67") (name "unconnected-(U$2-PadEXTRA27)") (class "Default")
      (node (ref "U$2") (pin "EXTRA27") (pinfunction "EXTRA27_EXTRA27") (pintype "bidirectional"))
    )
    (net (code "68") (name "unconnected-(U$2-PadEXTRA28)") (class "Default")
      (node (ref "U$2") (pin "EXTRA28") (pinfunction "EXTRA28_EXTRA28") (pintype "bidirectional"))
    )
    (net (code "69") (name "unconnected-(U$2-PadEXTRA29)") (class "Default")
      (node (ref "U$2") (pin "EXTRA29") (pinfunction "EXTRA29_EXTRA29") (pintype "bidirectional"))
    )
    (net (code "70") (name "unconnected-(U$2-PadEXTRA30)") (class "Default")
      (node (ref "U$2") (pin "EXTRA30") (pinfunction "EXTRA30_EXTRA30") (pintype "bidirectional"))
    )
    (net (code "71") (name "unconnected-(U$2-PadEXTRA31)") (class "Default")
      (node (ref "U$2") (pin "EXTRA31") (pinfunction "EXTRA31_EXTRA31") (pintype "bidirectional"))
    )
    (net (code "72") (name "unconnected-(U$2-PadEXTRA32)") (class "Default")
      (node (ref "U$2") (pin "EXTRA32") (pinfunction "EXTRA32_EXTRA32") (pintype "bidirectional"))
    )
    (net (code "73") (name "unconnected-(U$2-PadEXTRA33)") (class "Default")
      (node (ref "U$2") (pin "EXTRA33") (pinfunction "EXTRA33_EXTRA33") (pintype "bidirectional"))
    )
    (net (code "74") (name "unconnected-(U$2-PadEXTRA34)") (class "Default")
      (node (ref "U$2") (pin "EXTRA34") (pinfunction "EXTRA34_EXTRA34") (pintype "bidirectional"))
    )
    (net (code "75") (name "unconnected-(U$2-PadEXTRA35)") (class "Default")
      (node (ref "U$2") (pin "EXTRA35") (pinfunction "EXTRA35_EXTRA35") (pintype "bidirectional"))
    )
    (net (code "76") (name "unconnected-(U$2-PadKILL_SWITCH)") (class "Default")
      (node (ref "U$2") (pin "KILL_SWITCH") (pinfunction "KILL_SWITCH_KILL_SWITCH") (pintype "bidirectional"))
    )
    (net (code "77") (name "unconnected-(U$2-PadSCL_DEPTH)") (class "Default")
      (node (ref "U$2") (pin "SCL_DEPTH") (pinfunction "SCL_DEPTH_SCL_DEPTH") (pintype "bidirectional"))
    )
    (net (code "78") (name "unconnected-(U$2-PadSCL_SENSOR)") (class "Default")
      (node (ref "U$2") (pin "SCL_SENSOR") (pinfunction "SCL_SENSOR_SCL_SENSOR") (pintype "bidirectional"))
    )
    (net (code "79") (name "unconnected-(U$2-PadSDA_DEPTH)") (class "Default")
      (node (ref "U$2") (pin "SDA_DEPTH") (pinfunction "SDA_DEPTH_SDA_DEPTH") (pintype "bidirectional"))
    )
    (net (code "80") (name "unconnected-(U$2-PadSDA_SENSOR)") (class "Default")
      (node (ref "U$2") (pin "SDA_SENSOR") (pinfunction "SDA_SENSOR_SDA_SENSOR") (pintype "bidirectional"))
    )
  )
)
